# vga_wifi.net
KiCad netlist of a schematic drawn in EAGLE
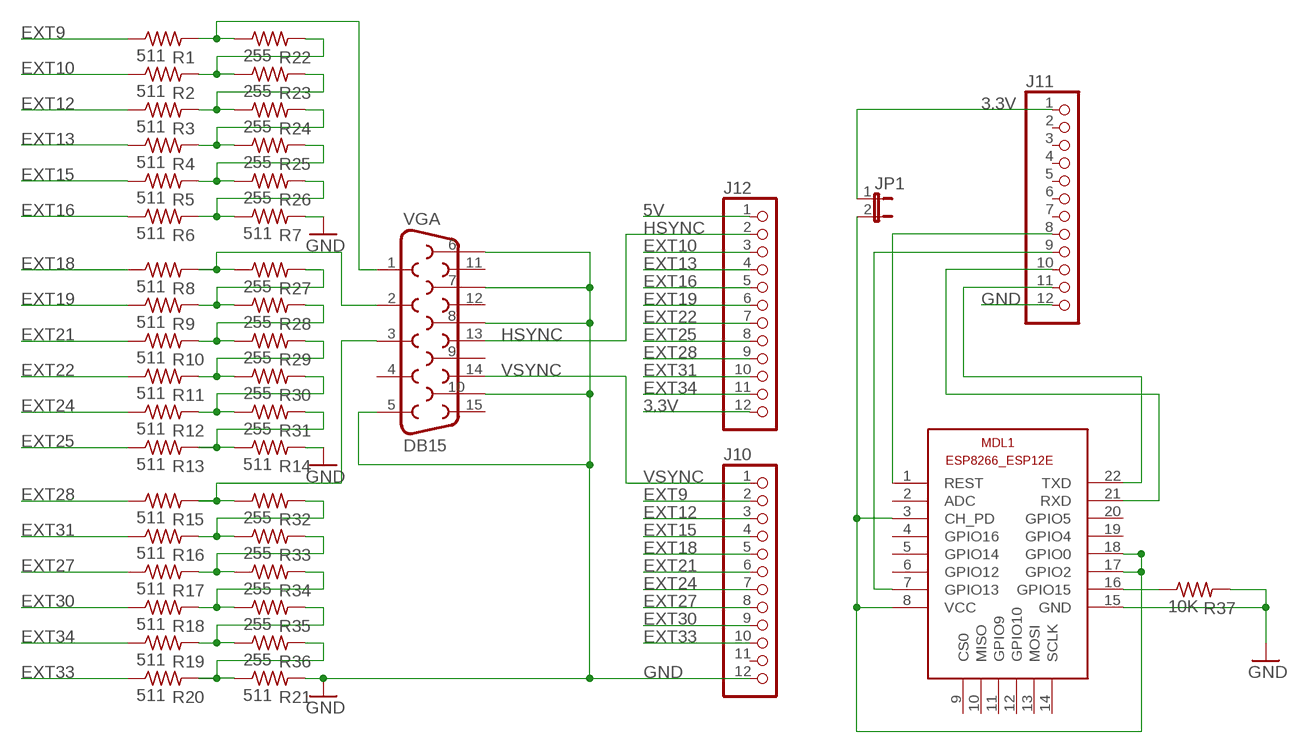
[diagram p0: schematic, sheet 1]

(export (version "E")
  (design (tool "Eeschema 10.0.6"))
  (components
    (comp (ref "J10")
      (value "PINHD-1X12")
      (footprint "eagle-import:1X12")
      (libsource (lib "eagle-import") (part "PINHD-1X12"))
    )
    (comp (ref "J11")
      (value "PINHD-1X12")
      (footprint "eagle-import:1X12")
      (libsource (lib "eagle-import") (part "PINHD-1X12"))
    )
    (comp (ref "J12")
      (value "PINHD-1X12")
      (footprint "eagle-import:1X12")
      (libsource (lib "eagle-import") (part "PINHD-1X12"))
    )
    (comp (ref "JP1")
      (value "JP1E")
      (footprint "eagle-import:JP1")
      (libsource (lib "eagle-import") (part "JP1E"))
    )
    (comp (ref "MDL1")
      (value "ESP8266-12EESP8266-ESP12E")
      (footprint "eagle-import:ESP8266-ESP12E")
      (libsource (lib "eagle-import") (part "ESP8266-12EESP8266-ESP12E"))
    )
    (comp (ref "R1")
      (value "511")
      (footprint "eagle-import:R0805")
      (libsource (lib "eagle-import") (part "R-US_R0805"))
    )
    (comp (ref "R2")
      (value "511")
      (footprint "eagle-import:R0805")
      (libsource (lib "eagle-import") (part "R-US_R0805"))
    )
    (comp (ref "R3")
      (value "511")
      (footprint "eagle-import:R0805")
      (libsource (lib "eagle-import") (part "R-US_R0805"))
    )
    (comp (ref "R4")
      (value "511")
      (footprint "eagle-import:R0805")
      (libsource (lib "eagle-import") (part "R-US_R0805"))
    )
    (comp (ref "R5")
      (value "511")
      (footprint "eagle-import:R0805")
      (libsource (lib "eagle-import") (part "R-US_R0805"))
    )
    (comp (ref "R6")
      (value "511")
      (footprint "eagle-import:R0805")
      (libsource (lib "eagle-import") (part "R-US_R0805"))
    )
    (comp (ref "R7")
      (value "511")
      (footprint "eagle-import:R0805")
      (libsource (lib "eagle-import") (part "R-US_R0805"))
    )
    (comp (ref "R8")
      (value "511")
      (footprint "eagle-import:R0805")
      (libsource (lib "eagle-import") (part "R-US_R0805"))
    )
    (comp (ref "R9")
      (value "511")
      (footprint "eagle-import:R0805")
      (libsource (lib "eagle-import") (part "R-US_R0805"))
    )
    (comp (ref "R10")
      (value "511")
      (footprint "eagle-import:R0805")
      (libsource (lib "eagle-import") (part "R-US_R0805"))
    )
    (comp (ref "R11")
      (value "511")
      (footprint "eagle-import:R0805")
      (libsource (lib "eagle-import") (part "R-US_R0805"))
    )
    (comp (ref "R12")
      (value "511")
      (footprint "eagle-import:R0805")
      (libsource (lib "eagle-import") (part "R-US_R0805"))
    )
    (comp (ref "R13")
      (value "511")
      (footprint "eagle-import:R0805")
      (libsource (lib "eagle-import") (part "R-US_R0805"))
    )
    (comp (ref "R14")
      (value "511")
      (footprint "eagle-import:R0805")
      (libsource (lib "eagle-import") (part "R-US_R0805"))
    )
    (comp (ref "R15")
      (value "511")
      (footprint "eagle-import:R0805")
      (libsource (lib "eagle-import") (part "R-US_R0805"))
    )
    (comp (ref "R16")
      (value "511")
      (footprint "eagle-import:R0805")
      (libsource (lib "eagle-import") (part "R-US_R0805"))
    )
    (comp (ref "R17")
      (value "511")
      (footprint "eagle-import:R0805")
      (libsource (lib "eagle-import") (part "R-US_R0805"))
    )
    (comp (ref "R18")
      (value "511")
      (footprint "eagle-import:R0805")
      (libsource (lib "eagle-import") (part "R-US_R0805"))
    )
    (comp (ref "R19")
      (value "511")
      (footprint "eagle-import:R0805")
      (libsource (lib "eagle-import") (part "R-US_R0805"))
    )
    (comp (ref "R20")
      (value "511")
      (footprint "eagle-import:R0805")
      (libsource (lib "eagle-import") (part "R-US_R0805"))
    )
    (comp (ref "R21")
      (value "511")
      (footprint "eagle-import:R0805")
      (libsource (lib "eagle-import") (part "R-US_R0805"))
    )
    (comp (ref "R22")
      (value "255")
      (footprint "eagle-import:R0805")
      (libsource (lib "eagle-import") (part "R-US_R0805"))
    )
    (comp (ref "R23")
      (value "255")
      (footprint "eagle-import:R0805")
      (libsource (lib "eagle-import") (part "R-US_R0805"))
    )
    (comp (ref "R24")
      (value "255")
      (footprint "eagle-import:R0805")
      (libsource (lib "eagle-import") (part "R-US_R0805"))
    )
    (comp (ref "R25")
      (value "255")
      (footprint "eagle-import:R0805")
      (libsource (lib "eagle-import") (part "R-US_R0805"))
    )
    (comp (ref "R26")
      (value "255")
      (footprint "eagle-import:R0805")
      (libsource (lib "eagle-import") (part "R-US_R0805"))
    )
    (comp (ref "R27")
      (value "255")
      (footprint "eagle-import:R0805")
      (libsource (lib "eagle-import") (part "R-US_R0805"))
    )
    (comp (ref "R28")
      (value "255")
      (footprint "eagle-import:R0805")
      (libsource (lib "eagle-import") (part "R-US_R0805"))
    )
    (comp (ref "R29")
      (value "255")
      (footprint "eagle-import:R0805")
      (libsource (lib "eagle-import") (part "R-US_R0805"))
    )
    (comp (ref "R30")
      (value "255")
      (footprint "eagle-import:R0805")
      (libsource (lib "eagle-import") (part "R-US_R0805"))
    )
    (comp (ref "R31")
      (value "255")
      (footprint "eagle-import:R0805")
      (libsource (lib "eagle-import") (part "R-US_R0805"))
    )
    (comp (ref "R32")
      (value "255")
      (footprint "eagle-import:R0805")
      (libsource (lib "eagle-import") (part "R-US_R0805"))
    )
    (comp (ref "R33")
      (value "255")
      (footprint "eagle-import:R0805")
      (libsource (lib "eagle-import") (part "R-US_R0805"))
    )
    (comp (ref "R34")
      (value "255")
      (footprint "eagle-import:R0805")
      (libsource (lib "eagle-import") (part "R-US_R0805"))
    )
    (comp (ref "R35")
      (value "255")
      (footprint "eagle-import:R0805")
      (libsource (lib "eagle-import") (part "R-US_R0805"))
    )
    (comp (ref "R36")
      (value "255")
      (footprint "eagle-import:R0805")
      (libsource (lib "eagle-import") (part "R-US_R0805"))
    )
    (comp (ref "R37")
      (value "10K")
      (footprint "eagle-import:R0805")
      (libsource (lib "eagle-import") (part "R-US_R0805"))
    )
    (comp (ref "VGA")
      (value "DB15")
      (footprint "eagle-import:DB15")
      (libsource (lib "eagle-import") (part "DB15"))
    )
  )
  (nets
    (net (code "1") (name "/3.3V") (class "Default")
      (node (ref "J11") (pin "1") (pinfunction "1_1") (pintype "passive"))
      (node (ref "J12") (pin "12") (pinfunction "12_12") (pintype "passive"))
      (node (ref "JP1") (pin "1") (pinfunction "1_1") (pintype "passive"))
    )
    (net (code "2") (name "/5V") (class "Default")
      (node (ref "J12") (pin "1") (pinfunction "1_1") (pintype "passive"))
    )
    (net (code "3") (name "/EXT9") (class "Default")
      (node (ref "J10") (pin "2") (pinfunction "2_2") (pintype "passive"))
      (node (ref "R1") (pin "1") (pinfunction "1_1") (pintype "passive"))
    )
    (net (code "4") (name "/EXT10") (class "Default")
      (node (ref "J12") (pin "3") (pinfunction "3_3") (pintype "passive"))
      (node (ref "R2") (pin "1") (pinfunction "1_1") (pintype "passive"))
    )
    (net (code "5") (name "/EXT12") (class "Default")
      (node (ref "J10") (pin "3") (pinfunction "3_3") (pintype "passive"))
      (node (ref "R3") (pin "1") (pinfunction "1_1") (pintype "passive"))
    )
    (net (code "6") (name "/EXT13") (class "Default")
      (node (ref "J12") (pin "4") (pinfunction "4_4") (pintype "passive"))
      (node (ref "R4") (pin "1") (pinfunction "1_1") (pintype "passive"))
    )
    (net (code "7") (name "/EXT15") (class "Default")
      (node (ref "J10") (pin "4") (pinfunction "4_4") (pintype "passive"))
      (node (ref "R5") (pin "1") (pinfunction "1_1") (pintype "passive"))
    )
    (net (code "8") (name "/EXT16") (class "Default")
      (node (ref "J12") (pin "5") (pinfunction "5_5") (pintype "passive"))
      (node (ref "R6") (pin "1") (pinfunction "1_1") (pintype "passive"))
    )
    (net (code "9") (name "/EXT18") (class "Default")
      (node (ref "J10") (pin "5") (pinfunction "5_5") (pintype "passive"))
      (node (ref "R8") (pin "1") (pinfunction "1_1") (pintype "passive"))
    )
    (net (code "10") (name "/EXT19") (class "Default")
      (node (ref "J12") (pin "6") (pinfunction "6_6") (pintype "passive"))
      (node (ref "R9") (pin "1") (pinfunction "1_1") (pintype "passive"))
    )
    (net (code "11") (name "/EXT21") (class "Default")
      (node (ref "J10") (pin "6") (pinfunction "6_6") (pintype "passive"))
      (node (ref "R10") (pin "1") (pinfunction "1_1") (pintype "passive"))
    )
    (net (code "12") (name "/EXT22") (class "Default")
      (node (ref "J12") (pin "7") (pinfunction "7_7") (pintype "passive"))
      (node (ref "R11") (pin "1") (pinfunction "1_1") (pintype "passive"))
    )
    (net (code "13") (name "/EXT24") (class "Default")
      (node (ref "J10") (pin "7") (pinfunction "7_7") (pintype "passive"))
      (node (ref "R12") (pin "1") (pinfunction "1_1") (pintype "passive"))
    )
    (net (code "14") (name "/EXT25") (class "Default")
      (node (ref "J12") (pin "8") (pinfunction "8_8") (pintype "passive"))
      (node (ref "R13") (pin "1") (pinfunction "1_1") (pintype "passive"))
    )
    (net (code "15") (name "/EXT27") (class "Default")
      (node (ref "J10") (pin "8") (pinfunction "8_8") (pintype "passive"))
      (node (ref "R17") (pin "1") (pinfunction "1_1") (pintype "passive"))
    )
    (net (code "16") (name "/EXT28") (class "Default")
      (node (ref "J12") (pin "9") (pinfunction "9_9") (pintype "passive"))
      (node (ref "R15") (pin "1") (pinfunction "1_1") (pintype "passive"))
    )
    (net (code "17") (name "/EXT30") (class "Default")
      (node (ref "J10") (pin "9") (pinfunction "9_9") (pintype "passive"))
      (node (ref "R18") (pin "1") (pinfunction "1_1") (pintype "passive"))
    )
    (net (code "18") (name "/EXT31") (class "Default")
      (node (ref "J12") (pin "10") (pinfunction "10_10") (pintype "passive"))
      (node (ref "R16") (pin "1") (pinfunction "1_1") (pintype "passive"))
    )
    (net (code "19") (name "/EXT33") (class "Default")
      (node (ref "J10") (pin "10") (pinfunction "10_10") (pintype "passive"))
      (node (ref "R20") (pin "1") (pinfunction "1_1") (pintype "passive"))
    )
    (net (code "20") (name "/EXT34") (class "Default")
      (node (ref "J12") (pin "11") (pinfunction "11_11") (pintype "passive"))
      (node (ref "R19") (pin "1") (pinfunction "1_1") (pintype "passive"))
    )
    (net (code "21") (name "/HSYNC") (class "Default")
      (node (ref "J12") (pin "2") (pinfunction "2_2") (pintype "passive"))
      (node (ref "VGA") (pin "13") (pinfunction "13_13") (pintype "passive"))
    )
    (net (code "22") (name "/VSYNC") (class "Default")
      (node (ref "J10") (pin "1") (pinfunction "1_1") (pintype "passive"))
      (node (ref "VGA") (pin "14") (pinfunction "14_14") (pintype "passive"))
    )
    (net (code "23") (name "GND") (class "Default")
      (node (ref "J10") (pin "12") (pinfunction "12_12") (pintype "passive"))
      (node (ref "J11") (pin "12") (pinfunction "12_12") (pintype "passive"))
      (node (ref "MDL1") (pin "15") (pinfunction "GND_15") (pintype "bidirectional"))
      (node (ref "R14") (pin "2") (pinfunction "2_2") (pintype "passive"))
      (node (ref "R21") (pin "2") (pinfunction "2_2") (pintype "passive"))
      (node (ref "R37") (pin "2") (pinfunction "2_2") (pintype "passive"))
      (node (ref "R7") (pin "2") (pinfunction "2_2") (pintype "passive"))
      (node (ref "VGA") (pin "10") (pinfunction "10_10") (pintype "passive"))
      (node (ref "VGA") (pin "5") (pinfunction "5_5") (pintype "passive"))
      (node (ref "VGA") (pin "6") (pinfunction "6_6") (pintype "passive"))
      (node (ref "VGA") (pin "7") (pinfunction "7_7") (pintype "passive"))
      (node (ref "VGA") (pin "8") (pinfunction "8_8") (pintype "passive"))
    )
    (net (code "24") (name "Net-(MDL1-CH_PD)") (class "Default")
      (node (ref "JP1") (pin "2") (pinfunction "2_2") (pintype "passive"))
      (node (ref "MDL1") (pin "17") (pinfunction "GPIO2_17") (pintype "bidirectional"))
      (node (ref "MDL1") (pin "18") (pinfunction "GPIO0_18") (pintype "bidirectional"))
      (node (ref "MDL1") (pin "3") (pinfunction "CH_PD_3") (pintype "bidirectional"))
      (node (ref "MDL1") (pin "8") (pinfunction "VCC_8") (pintype "bidirectional"))
    )
    (net (code "25") (name "Net-(MDL1-GPIO13)") (class "Default")
      (node (ref "J11") (pin "9") (pinfunction "9_9") (pintype "passive"))
      (node (ref "MDL1") (pin "7") (pinfunction "GPIO13_7") (pintype "bidirectional"))
    )
    (net (code "26") (name "Net-(MDL1-GPIO15)") (class "Default")
      (node (ref "MDL1") (pin "16") (pinfunction "GPIO15_16") (pintype "bidirectional"))
      (node (ref "R37") (pin "1") (pinfunction "1_1") (pintype "passive"))
    )
    (net (code "27") (name "Net-(MDL1-REST)") (class "Default")
      (node (ref "J11") (pin "8") (pinfunction "8_8") (pintype "passive"))
      (node (ref "MDL1") (pin "1") (pinfunction "REST_1") (pintype "bidirectional"))
    )
    (net (code "28") (name "Net-(MDL1-RXD)") (class "Default")
      (node (ref "J11") (pin "10") (pinfunction "10_10") (pintype "passive"))
      (node (ref "MDL1") (pin "21") (pinfunction "RXD_21") (pintype "bidirectional"))
    )
    (net (code "29") (name "Net-(MDL1-TXD)") (class "Default")
      (node (ref "J11") (pin "11") (pinfunction "11_11") (pintype "passive"))
      (node (ref "MDL1") (pin "22") (pinfunction "TXD_22") (pintype "bidirectional"))
    )
    (net (code "30") (name "Net-(R1-Pad2)") (class "Default")
      (node (ref "R1") (pin "2") (pinfunction "2_2") (pintype "passive"))
      (node (ref "R22") (pin "1") (pinfunction "1_1") (pintype "passive"))
      (node (ref "VGA") (pin "1") (pinfunction "1_1") (pintype "passive"))
    )
    (net (code "31") (name "Net-(R2-Pad2)") (class "Default")
      (node (ref "R2") (pin "2") (pinfunction "2_2") (pintype "passive"))
      (node (ref "R22") (pin "2") (pinfunction "2_2") (pintype "passive"))
      (node (ref "R23") (pin "1") (pinfunction "1_1") (pintype "passive"))
    )
    (net (code "32") (name "Net-(R10-Pad2)") (class "Default")
      (node (ref "R10") (pin "2") (pinfunction "2_2") (pintype "passive"))
      (node (ref "R28") (pin "2") (pinfunction "2_2") (pintype "passive"))
      (node (ref "R29") (pin "1") (pinfunction "1_1") (pintype "passive"))
    )
    (net (code "33") (name "Net-(R11-Pad2)") (class "Default")
      (node (ref "R11") (pin "2") (pinfunction "2_2") (pintype "passive"))
      (node (ref "R29") (pin "2") (pinfunction "2_2") (pintype "passive"))
      (node (ref "R30") (pin "1") (pinfunction "1_1") (pintype "passive"))
    )
    (net (code "34") (name "Net-(R12-Pad2)") (class "Default")
      (node (ref "R12") (pin "2") (pinfunction "2_2") (pintype "passive"))
      (node (ref "R30") (pin "2") (pinfunction "2_2") (pintype "passive"))
      (node (ref "R31") (pin "1") (pinfunction "1_1") (pintype "passive"))
    )
    (net (code "35") (name "Net-(R13-Pad2)") (class "Default")
      (node (ref "R13") (pin "2") (pinfunction "2_2") (pintype "passive"))
      (node (ref "R14") (pin "1") (pinfunction "1_1") (pintype "passive"))
      (node (ref "R31") (pin "2") (pinfunction "2_2") (pintype "passive"))
    )
    (net (code "36") (name "Net-(R15-Pad2)") (class "Default")
      (node (ref "R15") (pin "2") (pinfunction "2_2") (pintype "passive"))
      (node (ref "R32") (pin "1") (pinfunction "1_1") (pintype "passive"))
      (node (ref "VGA") (pin "3") (pinfunction "3_3") (pintype "passive"))
    )
    (net (code "37") (name "Net-(R16-Pad2)") (class "Default")
      (node (ref "R16") (pin "2") (pinfunction "2_2") (pintype "passive"))
      (node (ref "R32") (pin "2") (pinfunction "2_2") (pintype "passive"))
      (node (ref "R33") (pin "1") (pinfunction "1_1") (pintype "passive"))
    )
    (net (code "38") (name "Net-(R17-Pad2)") (class "Default")
      (node (ref "R17") (pin "2") (pinfunction "2_2") (pintype "passive"))
      (node (ref "R33") (pin "2") (pinfunction "2_2") (pintype "passive"))
      (node (ref "R34") (pin "1") (pinfunction "1_1") (pintype "passive"))
    )
    (net (code "39") (name "Net-(R18-Pad2)") (class "Default")
      (node (ref "R18") (pin "2") (pinfunction "2_2") (pintype "passive"))
      (node (ref "R34") (pin "2") (pinfunction "2_2") (pintype "passive"))
      (node (ref "R35") (pin "1") (pinfunction "1_1") (pintype "passive"))
    )
    (net (code "40") (name "Net-(R19-Pad2)") (class "Default")
      (node (ref "R19") (pin "2") (pinfunction "2_2") (pintype "passive"))
      (node (ref "R35") (pin "2") (pinfunction "2_2") (pintype "passive"))
      (node (ref "R36") (pin "1") (pinfunction "1_1") (pintype "passive"))
    )
    (net (code "41") (name "Net-(R20-Pad2)") (class "Default")
      (node (ref "R20") (pin "2") (pinfunction "2_2") (pintype "passive"))
      (node (ref "R21") (pin "1") (pinfunction "1_1") (pintype "passive"))
      (node (ref "R36") (pin "2") (pinfunction "2_2") (pintype "passive"))
    )
    (net (code "42") (name "Net-(R23-Pad2)") (class "Default")
      (node (ref "R23") (pin "2") (pinfunction "2_2") (pintype "passive"))
      (node (ref "R24") (pin "1") (pinfunction "1_1") (pintype "passive"))
      (node (ref "R3") (pin "2") (pinfunction "2_2") (pintype "passive"))
    )
    (net (code "43") (name "Net-(R24-Pad2)") (class "Default")
      (node (ref "R24") (pin "2") (pinfunction "2_2") (pintype "passive"))
      (node (ref "R25") (pin "1") (pinfunction "1_1") (pintype "passive"))
      (node (ref "R4") (pin "2") (pinfunction "2_2") (pintype "passive"))
    )
    (net (code "44") (name "Net-(R25-Pad2)") (class "Default")
      (node (ref "R25") (pin "2") (pinfunction "2_2") (pintype "passive"))
      (node (ref "R26") (pin "1") (pinfunction "1_1") (pintype "passive"))
      (node (ref "R5") (pin "2") (pinfunction "2_2") (pintype "passive"))
    )
    (net (code "45") (name "Net-(R26-Pad2)") (class "Default")
      (node (ref "R26") (pin "2") (pinfunction "2_2") (pintype "passive"))
      (node (ref "R6") (pin "2") (pinfunction "2_2") (pintype "passive"))
      (node (ref "R7") (pin "1") (pinfunction "1_1") (pintype "passive"))
    )
    (net (code "46") (name "Net-(R27-Pad1)") (class "Default")
      (node (ref "R27") (pin "1") (pinfunction "1_1") (pintype "passive"))
      (node (ref "R8") (pin "2") (pinfunction "2_2") (pintype "passive"))
      (node (ref "VGA") (pin "2") (pinfunction "2_2") (pintype "passive"))
    )
    (net (code "47") (name "Net-(R27-Pad2)") (class "Default")
      (node (ref "R27") (pin "2") (pinfunction "2_2") (pintype "passive"))
      (node (ref "R28") (pin "1") (pinfunction "1_1") (pintype "passive"))
      (node (ref "R9") (pin "2") (pinfunction "2_2") (pintype "passive"))
    )
    (net (code "48") (name "unconnected-(J10-Pad11)") (class "Default")
      (node (ref "J10") (pin "11") (pinfunction "11_11") (pintype "passive"))
    )
    (net (code "49") (name "unconnected-(J11-Pad2)") (class "Default")
      (node (ref "J11") (pin "2") (pinfunction "2_2") (pintype "passive"))
    )
    (net (code "50") (name "unconnected-(J11-Pad3)") (class "Default")
      (node (ref "J11") (pin "3") (pinfunction "3_3") (pintype "passive"))
    )
    (net (code "51") (name "unconnected-(J11-Pad4)") (class "Default")
      (node (ref "J11") (pin "4") (pinfunction "4_4") (pintype "passive"))
    )
    (net (code "52") (name "unconnected-(J11-Pad5)") (class "Default")
      (node (ref "J11") (pin "5") (pinfunction "5_5") (pintype "passive"))
    )
    (net (code "53") (name "unconnected-(J11-Pad6)") (class "Default")
      (node (ref "J11") (pin "6") (pinfunction "6_6") (pintype "passive"))
    )
    (net (code "54") (name "unconnected-(J11-Pad7)") (class "Default")
      (node (ref "J11") (pin "7") (pinfunction "7_7") (pintype "passive"))
    )
    (net (code "55") (name "unconnected-(MDL1-ADC-Pad2)") (class "Default")
      (node (ref "MDL1") (pin "2") (pinfunction "ADC_2") (pintype "bidirectional"))
    )
    (net (code "56") (name "unconnected-(MDL1-CS0-Pad9)") (class "Default")
      (node (ref "MDL1") (pin "9") (pinfunction "CS0_9") (pintype "bidirectional"))
    )
    (net (code "57") (name "unconnected-(MDL1-GPIO4-Pad19)") (class "Default")
      (node (ref "MDL1") (pin "19") (pinfunction "GPIO4_19") (pintype "bidirectional"))
    )
    (net (code "58") (name "unconnected-(MDL1-GPIO5-Pad20)") (class "Default")
      (node (ref "MDL1") (pin "20") (pinfunction "GPIO5_20") (pintype "bidirectional"))
    )
    (net (code "59") (name "unconnected-(MDL1-GPIO9-Pad11)") (class "Default")
      (node (ref "MDL1") (pin "11") (pinfunction "GPIO9_11") (pintype "bidirectional"))
    )
    (net (code "60") (name "unconnected-(MDL1-GPIO10-Pad12)") (class "Default")
      (node (ref "MDL1") (pin "12") (pinfunction "GPIO10_12") (pintype "bidirectional"))
    )
    (net (code "61") (name "unconnected-(MDL1-GPIO12-Pad6)") (class "Default")
      (node (ref "MDL1") (pin "6") (pinfunction "GPIO12_6") (pintype "bidirectional"))
    )
    (net (code "62") (name "unconnected-(MDL1-GPIO14-Pad5)") (class "Default")
      (node (ref "MDL1") (pin "5") (pinfunction "GPIO14_5") (pintype "bidirectional"))
    )
    (net (code "63") (name "unconnected-(MDL1-GPIO16-Pad4)") (class "Default")
      (node (ref "MDL1") (pin "4") (pinfunction "GPIO16_4") (pintype "bidirectional"))
    )
    (net (code "64") (name "unconnected-(MDL1-MISO-Pad10)") (class "Default")
      (node (ref "MDL1") (pin "10") (pinfunction "MISO_10") (pintype "bidirectional"))
    )
    (net (code "65") (name "unconnected-(MDL1-MOSI-Pad13)") (class "Default")
      (node (ref "MDL1") (pin "13") (pinfunction "MOSI_13") (pintype "bidirectional"))
    )
    (net (code "66") (name "unconnected-(MDL1-SCLK-Pad14)") (class "Default")
      (node (ref "MDL1") (pin "14") (pinfunction "SCLK_14") (pintype "bidirectional"))
    )
    (net (code "67") (name "unconnected-(VGA-Pad4)") (class "Default")
      (node (ref "VGA") (pin "4") (pinfunction "4_4") (pintype "passive"))
    )
    (net (code "68") (name "unconnected-(VGA-Pad9)") (class "Default")
      (node (ref "VGA") (pin "9") (pinfunction "9_9") (pintype "passive"))
    )
    (net (code "69") (name "unconnected-(VGA-Pad11)") (class "Default")
      (node (ref "VGA") (pin "11") (pinfunction "11_11") (pintype "passive"))
    )
    (net (code "70") (name "unconnected-(VGA-Pad12)") (class "Default")
      (node (ref "VGA") (pin "12") (pinfunction "12_12") (pintype "passive"))
    )
    (net (code "71") (name "unconnected-(VGA-Pad15)") (class "Default")
      (node (ref "VGA") (pin "15") (pinfunction "15_15") (pintype "passive"))
    )
  )
)
